# Vjtronics_wo_GND.net
KiCad netlist of a schematic drawn in EAGLE
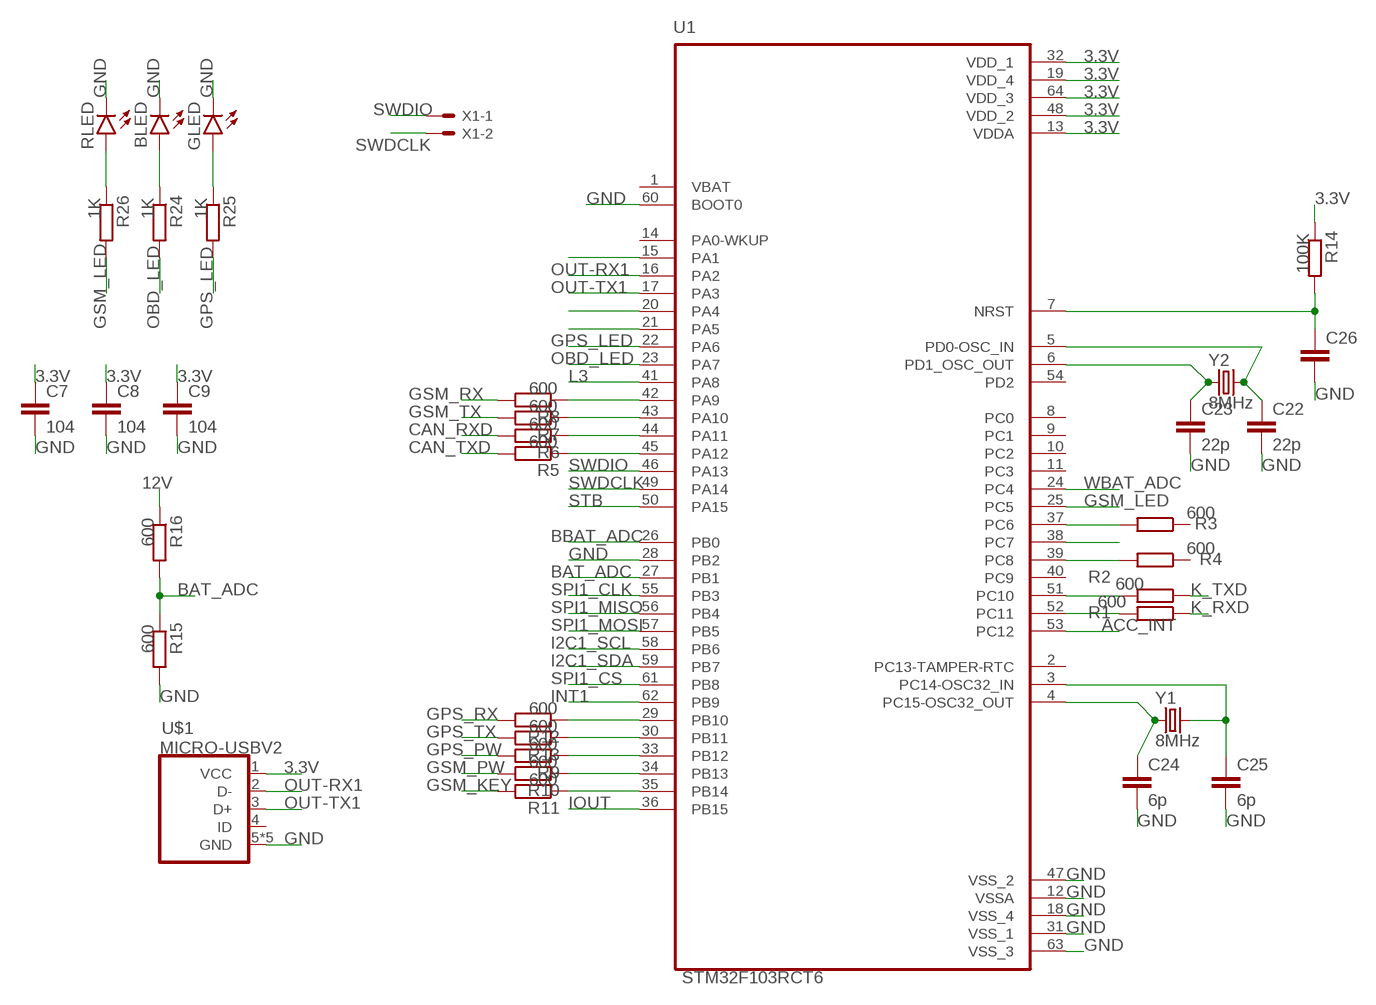
[diagram p0: schematic, sheet 1]

(export (version "E")
  (design (tool "Eeschema 10.0.6"))
  (components
    (comp (ref "BLED")
      (value "LEDCHIPLED_0805")
      (footprint "eagle-import:CHIPLED_0805")
      (libsource (lib "eagle-import") (part "LEDCHIPLED_0805"))
    )
    (comp (ref "C7")
      (value "104")
      (footprint "eagle-import:C0805")
      (libsource (lib "eagle-import") (part "C-EUC0805"))
    )
    (comp (ref "C8")
      (value "104")
      (footprint "eagle-import:C0805")
      (libsource (lib "eagle-import") (part "C-EUC0805"))
    )
    (comp (ref "C9")
      (value "104")
      (footprint "eagle-import:C0805")
      (libsource (lib "eagle-import") (part "C-EUC0805"))
    )
    (comp (ref "C22")
      (value "22p")
      (footprint "eagle-import:C0805")
      (libsource (lib "eagle-import") (part "C-EUC0805"))
    )
    (comp (ref "C23")
      (value "22p")
      (footprint "eagle-import:C0805")
      (libsource (lib "eagle-import") (part "C-EUC0805"))
    )
    (comp (ref "C24")
      (value "6p")
      (footprint "eagle-import:C0805")
      (libsource (lib "eagle-import") (part "C-EUC0805"))
    )
    (comp (ref "C25")
      (value "6p")
      (footprint "eagle-import:C0805")
      (libsource (lib "eagle-import") (part "C-EUC0805"))
    )
    (comp (ref "C26")
      (value "C-EUC0805")
      (footprint "eagle-import:C0805")
      (libsource (lib "eagle-import") (part "C-EUC0805"))
    )
    (comp (ref "GLED")
      (value "LEDCHIPLED_0805")
      (footprint "eagle-import:CHIPLED_0805")
      (libsource (lib "eagle-import") (part "LEDCHIPLED_0805"))
    )
    (comp (ref "R1")
      (value "600")
      (footprint "eagle-import:M0805")
      (libsource (lib "eagle-import") (part "R-EU_M0805"))
    )
    (comp (ref "R2")
      (value "600")
      (footprint "eagle-import:M0805")
      (libsource (lib "eagle-import") (part "R-EU_M0805"))
    )
    (comp (ref "R3")
      (value "600")
      (footprint "eagle-import:M0805")
      (libsource (lib "eagle-import") (part "R-EU_M0805"))
    )
    (comp (ref "R4")
      (value "600")
      (footprint "eagle-import:M0805")
      (libsource (lib "eagle-import") (part "R-EU_M0805"))
    )
    (comp (ref "R5")
      (value "600")
      (footprint "eagle-import:M0805")
      (libsource (lib "eagle-import") (part "R-EU_M0805"))
    )
    (comp (ref "R6")
      (value "600")
      (footprint "eagle-import:M0805")
      (libsource (lib "eagle-import") (part "R-EU_M0805"))
    )
    (comp (ref "R7")
      (value "600")
      (footprint "eagle-import:M0805")
      (libsource (lib "eagle-import") (part "R-EU_M0805"))
    )
    (comp (ref "R8")
      (value "600")
      (footprint "eagle-import:M0805")
      (libsource (lib "eagle-import") (part "R-EU_M0805"))
    )
    (comp (ref "R9")
      (value "600")
      (footprint "eagle-import:M0805")
      (libsource (lib "eagle-import") (part "R-EU_M0805"))
    )
    (comp (ref "R10")
      (value "600")
      (footprint "eagle-import:M0805")
      (libsource (lib "eagle-import") (part "R-EU_M0805"))
    )
    (comp (ref "R11")
      (value "600")
      (footprint "eagle-import:M0805")
      (libsource (lib "eagle-import") (part "R-EU_M0805"))
    )
    (comp (ref "R12")
      (value "600")
      (footprint "eagle-import:M0805")
      (libsource (lib "eagle-import") (part "R-EU_M0805"))
    )
    (comp (ref "R13")
      (value "600")
      (footprint "eagle-import:M0805")
      (libsource (lib "eagle-import") (part "R-EU_M0805"))
    )
    (comp (ref "R14")
      (value "100K")
      (footprint "eagle-import:M0805")
      (libsource (lib "eagle-import") (part "R-EU_M0805"))
    )
    (comp (ref "R15")
      (value "600")
      (footprint "eagle-import:M0805")
      (libsource (lib "eagle-import") (part "R-EU_M0805"))
    )
    (comp (ref "R16")
      (value "600")
      (footprint "eagle-import:M0805")
      (libsource (lib "eagle-import") (part "R-EU_M0805"))
    )
    (comp (ref "R24")
      (value "1K")
      (footprint "eagle-import:M0805")
      (libsource (lib "eagle-import") (part "R-EU_M0805"))
    )
    (comp (ref "R25")
      (value "1K")
      (footprint "eagle-import:M0805")
      (libsource (lib "eagle-import") (part "R-EU_M0805"))
    )
    (comp (ref "R26")
      (value "1K")
      (footprint "eagle-import:M0805")
      (libsource (lib "eagle-import") (part "R-EU_M0805"))
    )
    (comp (ref "RLED")
      (value "LEDCHIPLED_0805")
      (footprint "eagle-import:CHIPLED_0805")
      (libsource (lib "eagle-import") (part "LEDCHIPLED_0805"))
    )
    (comp (ref "U$1")
      (value "MICRO-USBV2")
      (footprint "eagle-import:MICRO-USB-2")
      (libsource (lib "eagle-import") (part "MICRO-USBV2"))
    )
    (comp (ref "U1")
      (value "STM32F103RCT6")
      (footprint "eagle-import:QFP50P1200X1200X160-64N")
      (fields (field (name "MF") "STMicroelectronics"))
      (libsource (lib "eagle-import") (part "STM32F103RCT6"))
    )
    (comp (ref "X1")
      (value "22-23-2021")
      (footprint "eagle-import:22-23-2021")
      (libsource (lib "eagle-import") (part "22-23-2021"))
    )
    (comp (ref "Y1")
      (value "8MHz")
      (footprint "eagle-import:CSM-7X-DU")
      (libsource (lib "eagle-import") (part "CSM-7X-DU"))
    )
    (comp (ref "Y2")
      (value "8MHz")
      (footprint "eagle-import:CSM-7X-DU")
      (libsource (lib "eagle-import") (part "CSM-7X-DU"))
    )
  )
  (nets
    (net (code "1") (name "/3.3V") (class "Default")
      (node (ref "C7") (pin "1") (pinfunction "1_1") (pintype "passive"))
      (node (ref "C8") (pin "1") (pinfunction "1_1") (pintype "passive"))
      (node (ref "C9") (pin "1") (pinfunction "1_1") (pintype "passive"))
      (node (ref "R14") (pin "1") (pinfunction "1_1") (pintype "passive"))
      (node (ref "U$1") (pin "1") (pinfunction "VCC_1") (pintype "power_in"))
      (node (ref "U1") (pin "13") (pinfunction "VDDA_13") (pintype "power_in"))
      (node (ref "U1") (pin "19") (pinfunction "VDD_4_19") (pintype "power_in"))
      (node (ref "U1") (pin "32") (pinfunction "VDD_1_32") (pintype "power_in"))
      (node (ref "U1") (pin "48") (pinfunction "VDD_2_48") (pintype "power_in"))
      (node (ref "U1") (pin "64") (pinfunction "VDD_3_64") (pintype "power_in"))
    )
    (net (code "2") (name "/12V") (class "Default")
      (node (ref "R16") (pin "1") (pinfunction "1_1") (pintype "passive"))
    )
    (net (code "3") (name "/ACC_INT") (class "Default")
      (node (ref "U1") (pin "53") (pinfunction "PC12_53") (pintype "bidirectional"))
    )
    (net (code "4") (name "/BAT_ADC") (class "Default")
      (node (ref "R15") (pin "1") (pinfunction "1_1") (pintype "passive"))
      (node (ref "R16") (pin "2") (pinfunction "2_2") (pintype "passive"))
      (node (ref "U1") (pin "27") (pinfunction "PB1_27") (pintype "bidirectional"))
    )
    (net (code "5") (name "/BBAT_ADC") (class "Default")
      (node (ref "U1") (pin "26") (pinfunction "PB0_26") (pintype "bidirectional"))
    )
    (net (code "6") (name "/CAN_RXD") (class "Default")
      (node (ref "R6") (pin "2") (pinfunction "2_2") (pintype "passive"))
    )
    (net (code "7") (name "/CAN_TXD") (class "Default")
      (node (ref "R5") (pin "2") (pinfunction "2_2") (pintype "passive"))
    )
    (net (code "8") (name "/GND") (class "Default")
      (node (ref "BLED") (pin "C") (pinfunction "C_C") (pintype "passive"))
      (node (ref "C22") (pin "2") (pinfunction "2_2") (pintype "passive"))
      (node (ref "C23") (pin "2") (pinfunction "2_2") (pintype "passive"))
      (node (ref "C24") (pin "2") (pinfunction "2_2") (pintype "passive"))
      (node (ref "C25") (pin "2") (pinfunction "2_2") (pintype "passive"))
      (node (ref "C26") (pin "2") (pinfunction "2_2") (pintype "passive"))
      (node (ref "C7") (pin "2") (pinfunction "2_2") (pintype "passive"))
      (node (ref "C8") (pin "2") (pinfunction "2_2") (pintype "passive"))
      (node (ref "C9") (pin "2") (pinfunction "2_2") (pintype "passive"))
      (node (ref "GLED") (pin "C") (pinfunction "C_C") (pintype "passive"))
      (node (ref "R15") (pin "2") (pinfunction "2_2") (pintype "passive"))
      (node (ref "RLED") (pin "C") (pinfunction "C_C") (pintype "passive"))
      (node (ref "U$1") (pin "5") (pinfunction "GND_5") (pintype "power_in"))
      (node (ref "U$1") (pin "P$1") (pinfunction "GND_P$1") (pintype "power_in"))
      (node (ref "U$1") (pin "P$2") (pinfunction "GND_P$2") (pintype "power_in"))
      (node (ref "U$1") (pin "P$3") (pinfunction "GND_P$3") (pintype "power_in"))
      (node (ref "U$1") (pin "P$4") (pinfunction "GND_P$4") (pintype "power_in"))
      (node (ref "U1") (pin "12") (pinfunction "VSSA_12") (pintype "power_in"))
      (node (ref "U1") (pin "18") (pinfunction "VSS_4_18") (pintype "power_in"))
      (node (ref "U1") (pin "28") (pinfunction "PB2_28") (pintype "bidirectional"))
      (node (ref "U1") (pin "31") (pinfunction "VSS_1_31") (pintype "power_in"))
      (node (ref "U1") (pin "47") (pinfunction "VSS_2_47") (pintype "power_in"))
      (node (ref "U1") (pin "60") (pinfunction "BOOT0_60") (pintype "input"))
      (node (ref "U1") (pin "63") (pinfunction "VSS_3_63") (pintype "power_in"))
    )
    (net (code "9") (name "/GPS_LED") (class "Default")
      (node (ref "R25") (pin "2") (pinfunction "2_2") (pintype "passive"))
      (node (ref "U1") (pin "22") (pinfunction "PA6_22") (pintype "bidirectional"))
    )
    (net (code "10") (name "/GPS_PW") (class "Default")
      (node (ref "R9") (pin "2") (pinfunction "2_2") (pintype "passive"))
    )
    (net (code "11") (name "/GPS_RX") (class "Default")
      (node (ref "R12") (pin "2") (pinfunction "2_2") (pintype "passive"))
    )
    (net (code "12") (name "/GPS_TX") (class "Default")
      (node (ref "R13") (pin "2") (pinfunction "2_2") (pintype "passive"))
    )
    (net (code "13") (name "/GSM_KEY") (class "Default")
      (node (ref "R11") (pin "2") (pinfunction "2_2") (pintype "passive"))
    )
    (net (code "14") (name "/GSM_LED") (class "Default")
      (node (ref "R26") (pin "2") (pinfunction "2_2") (pintype "passive"))
      (node (ref "U1") (pin "25") (pinfunction "PC5_25") (pintype "bidirectional"))
    )
    (net (code "15") (name "/GSM_PW") (class "Default")
      (node (ref "R10") (pin "2") (pinfunction "2_2") (pintype "passive"))
    )
    (net (code "16") (name "/GSM_RX") (class "Default")
      (node (ref "R8") (pin "2") (pinfunction "2_2") (pintype "passive"))
    )
    (net (code "17") (name "/GSM_TX") (class "Default")
      (node (ref "R7") (pin "2") (pinfunction "2_2") (pintype "passive"))
    )
    (net (code "18") (name "/I2C1_SCL") (class "Default")
      (node (ref "U1") (pin "58") (pinfunction "PB6_58") (pintype "bidirectional"))
    )
    (net (code "19") (name "/I2C1_SDA") (class "Default")
      (node (ref "U1") (pin "59") (pinfunction "PB7_59") (pintype "bidirectional"))
    )
    (net (code "20") (name "/INT1") (class "Default")
      (node (ref "U1") (pin "62") (pinfunction "PB9_62") (pintype "bidirectional"))
    )
    (net (code "21") (name "/IOUT") (class "Default")
      (node (ref "U1") (pin "36") (pinfunction "PB15_36") (pintype "bidirectional"))
    )
    (net (code "22") (name "/K_RXD") (class "Default")
      (node (ref "R1") (pin "1") (pinfunction "1_1") (pintype "passive"))
    )
    (net (code "23") (name "/K_TXD") (class "Default")
      (node (ref "R2") (pin "1") (pinfunction "1_1") (pintype "passive"))
    )
    (net (code "24") (name "/L3") (class "Default")
      (node (ref "U1") (pin "41") (pinfunction "PA8_41") (pintype "bidirectional"))
    )
    (net (code "25") (name "/OBD_LED") (class "Default")
      (node (ref "R24") (pin "2") (pinfunction "2_2") (pintype "passive"))
      (node (ref "U1") (pin "23") (pinfunction "PA7_23") (pintype "bidirectional"))
    )
    (net (code "26") (name "/OUT-RX1") (class "Default")
      (node (ref "U$1") (pin "2") (pinfunction "D-_2") (pintype "bidirectional"))
      (node (ref "U1") (pin "16") (pinfunction "PA2_16") (pintype "bidirectional"))
    )
    (net (code "27") (name "/OUT-TX1") (class "Default")
      (node (ref "U$1") (pin "3") (pinfunction "D+_3") (pintype "bidirectional"))
      (node (ref "U1") (pin "17") (pinfunction "PA3_17") (pintype "bidirectional"))
    )
    (net (code "28") (name "/SPI1_CLK") (class "Default")
      (node (ref "U1") (pin "55") (pinfunction "PB3_55") (pintype "bidirectional"))
    )
    (net (code "29") (name "/SPI1_CS") (class "Default")
      (node (ref "U1") (pin "61") (pinfunction "PB8_61") (pintype "bidirectional"))
    )
    (net (code "30") (name "/SPI1_MISO") (class "Default")
      (node (ref "U1") (pin "56") (pinfunction "PB4_56") (pintype "bidirectional"))
    )
    (net (code "31") (name "/SPI1_MOSI") (class "Default")
      (node (ref "U1") (pin "57") (pinfunction "PB5_57") (pintype "bidirectional"))
    )
    (net (code "32") (name "/STB") (class "Default")
      (node (ref "U1") (pin "50") (pinfunction "PA15_50") (pintype "bidirectional"))
    )
    (net (code "33") (name "/SWDCLK") (class "Default")
      (node (ref "U1") (pin "49") (pinfunction "PA14_49") (pintype "bidirectional"))
      (node (ref "X1") (pin "2") (pinfunction "S_2") (pintype "passive"))
    )
    (net (code "34") (name "/SWDIO") (class "Default")
      (node (ref "U1") (pin "46") (pinfunction "PA13_46") (pintype "bidirectional"))
      (node (ref "X1") (pin "1") (pinfunction "S_1") (pintype "passive"))
    )
    (net (code "35") (name "/WBAT_ADC") (class "Default")
      (node (ref "U1") (pin "24") (pinfunction "PC4_24") (pintype "bidirectional"))
    )
    (net (code "36") (name "Net-(BLED-PadA)") (class "Default")
      (node (ref "BLED") (pin "A") (pinfunction "A_A") (pintype "passive"))
      (node (ref "R24") (pin "1") (pinfunction "1_1") (pintype "passive"))
    )
    (net (code "37") (name "Net-(GLED-PadA)") (class "Default")
      (node (ref "GLED") (pin "A") (pinfunction "A_A") (pintype "passive"))
      (node (ref "R25") (pin "1") (pinfunction "1_1") (pintype "passive"))
    )
    (net (code "38") (name "Net-(R26-Pad1)") (class "Default")
      (node (ref "R26") (pin "1") (pinfunction "1_1") (pintype "passive"))
      (node (ref "RLED") (pin "A") (pinfunction "A_A") (pintype "passive"))
    )
    (net (code "39") (name "Net-(U1-NRST)") (class "Default")
      (node (ref "C26") (pin "1") (pinfunction "1_1") (pintype "passive"))
      (node (ref "R14") (pin "2") (pinfunction "2_2") (pintype "passive"))
      (node (ref "U1") (pin "7") (pinfunction "NRST_7") (pintype "input"))
    )
    (net (code "40") (name "Net-(U1-PA9)") (class "Default")
      (node (ref "R8") (pin "1") (pinfunction "1_1") (pintype "passive"))
      (node (ref "U1") (pin "42") (pinfunction "PA9_42") (pintype "bidirectional"))
    )
    (net (code "41") (name "Net-(U1-PA10)") (class "Default")
      (node (ref "R7") (pin "1") (pinfunction "1_1") (pintype "passive"))
      (node (ref "U1") (pin "43") (pinfunction "PA10_43") (pintype "bidirectional"))
    )
    (net (code "42") (name "Net-(U1-PA11)") (class "Default")
      (node (ref "R6") (pin "1") (pinfunction "1_1") (pintype "passive"))
      (node (ref "U1") (pin "44") (pinfunction "PA11_44") (pintype "bidirectional"))
    )
    (net (code "43") (name "Net-(U1-PA12)") (class "Default")
      (node (ref "R5") (pin "1") (pinfunction "1_1") (pintype "passive"))
      (node (ref "U1") (pin "45") (pinfunction "PA12_45") (pintype "bidirectional"))
    )
    (net (code "44") (name "Net-(U1-PB10)") (class "Default")
      (node (ref "R12") (pin "1") (pinfunction "1_1") (pintype "passive"))
      (node (ref "U1") (pin "29") (pinfunction "PB10_29") (pintype "bidirectional"))
    )
    (net (code "45") (name "Net-(U1-PB11)") (class "Default")
      (node (ref "R13") (pin "1") (pinfunction "1_1") (pintype "passive"))
      (node (ref "U1") (pin "30") (pinfunction "PB11_30") (pintype "bidirectional"))
    )
    (net (code "46") (name "Net-(U1-PB12)") (class "Default")
      (node (ref "R9") (pin "1") (pinfunction "1_1") (pintype "passive"))
      (node (ref "U1") (pin "33") (pinfunction "PB12_33") (pintype "bidirectional"))
    )
    (net (code "47") (name "Net-(U1-PB13)") (class "Default")
      (node (ref "R10") (pin "1") (pinfunction "1_1") (pintype "passive"))
      (node (ref "U1") (pin "34") (pinfunction "PB13_34") (pintype "bidirectional"))
    )
    (net (code "48") (name "Net-(U1-PB14)") (class "Default")
      (node (ref "R11") (pin "1") (pinfunction "1_1") (pintype "passive"))
      (node (ref "U1") (pin "35") (pinfunction "PB14_35") (pintype "bidirectional"))
    )
    (net (code "49") (name "Net-(U1-PC6)") (class "Default")
      (node (ref "R3") (pin "2") (pinfunction "2_2") (pintype "passive"))
      (node (ref "U1") (pin "37") (pinfunction "PC6_37") (pintype "bidirectional"))
    )
    (net (code "50") (name "Net-(U1-PC8)") (class "Default")
      (node (ref "R4") (pin "2") (pinfunction "2_2") (pintype "passive"))
      (node (ref "U1") (pin "39") (pinfunction "PC8_39") (pintype "bidirectional"))
    )
    (net (code "51") (name "Net-(U1-PC10)") (class "Default")
      (node (ref "R2") (pin "2") (pinfunction "2_2") (pintype "passive"))
      (node (ref "U1") (pin "51") (pinfunction "PC10_51") (pintype "bidirectional"))
    )
    (net (code "52") (name "Net-(U1-PC11)") (class "Default")
      (node (ref "R1") (pin "2") (pinfunction "2_2") (pintype "passive"))
      (node (ref "U1") (pin "52") (pinfunction "PC11_52") (pintype "bidirectional"))
    )
    (net (code "53") (name "Net-(U1-PC14-OSC32_IN)") (class "Default")
      (node (ref "C25") (pin "1") (pinfunction "1_1") (pintype "passive"))
      (node (ref "U1") (pin "3") (pinfunction "PC14-OSC32_IN_3") (pintype "bidirectional"))
      (node (ref "Y1") (pin "2") (pinfunction "2_2") (pintype "passive"))
    )
    (net (code "54") (name "Net-(U1-PC15-OSC32_OUT)") (class "Default")
      (node (ref "C24") (pin "1") (pinfunction "1_1") (pintype "passive"))
      (node (ref "U1") (pin "4") (pinfunction "PC15-OSC32_OUT_4") (pintype "bidirectional"))
      (node (ref "Y1") (pin "1") (pinfunction "1_1") (pintype "passive"))
    )
    (net (code "55") (name "Net-(U1-PD0-OSC_IN)") (class "Default")
      (node (ref "C22") (pin "1") (pinfunction "1_1") (pintype "passive"))
      (node (ref "U1") (pin "5") (pinfunction "PD0-OSC_IN_5") (pintype "input"))
      (node (ref "Y2") (pin "2") (pinfunction "2_2") (pintype "passive"))
    )
    (net (code "56") (name "Net-(U1-PD1_OSC_OUT)") (class "Default")
      (node (ref "C23") (pin "1") (pinfunction "1_1") (pintype "passive"))
      (node (ref "U1") (pin "6") (pinfunction "PD1_OSC_OUT_6") (pintype "output"))
      (node (ref "Y2") (pin "1") (pinfunction "1_1") (pintype "passive"))
    )
    (net (code "57") (name "unconnected-(R3-Pad1)") (class "Default")
      (node (ref "R3") (pin "1") (pinfunction "1_1") (pintype "passive"))
    )
    (net (code "58") (name "unconnected-(R4-Pad1)") (class "Default")
      (node (ref "R4") (pin "1") (pinfunction "1_1") (pintype "passive"))
    )
    (net (code "59") (name "unconnected-(U$1-ID-Pad4)") (class "Default")
      (node (ref "U$1") (pin "4") (pinfunction "ID_4") (pintype "bidirectional"))
    )
    (net (code "60") (name "unconnected-(U1-PA0-WKUP-Pad14)") (class "Default")
      (node (ref "U1") (pin "14") (pinfunction "PA0-WKUP_14") (pintype "bidirectional"))
    )
    (net (code "61") (name "unconnected-(U1-PA1-Pad15)") (class "Default")
      (node (ref "U1") (pin "15") (pinfunction "PA1_15") (pintype "bidirectional"))
    )
    (net (code "62") (name "unconnected-(U1-PA4-Pad20)") (class "Default")
      (node (ref "U1") (pin "20") (pinfunction "PA4_20") (pintype "bidirectional"))
    )
    (net (code "63") (name "unconnected-(U1-PA5-Pad21)") (class "Default")
      (node (ref "U1") (pin "21") (pinfunction "PA5_21") (pintype "bidirectional"))
    )
    (net (code "64") (name "unconnected-(U1-PC0-Pad8)") (class "Default")
      (node (ref "U1") (pin "8") (pinfunction "PC0_8") (pintype "bidirectional"))
    )
    (net (code "65") (name "unconnected-(U1-PC1-Pad9)") (class "Default")
      (node (ref "U1") (pin "9") (pinfunction "PC1_9") (pintype "bidirectional"))
    )
    (net (code "66") (name "unconnected-(U1-PC2-Pad10)") (class "Default")
      (node (ref "U1") (pin "10") (pinfunction "PC2_10") (pintype "bidirectional"))
    )
    (net (code "67") (name "unconnected-(U1-PC3-Pad11)") (class "Default")
      (node (ref "U1") (pin "11") (pinfunction "PC3_11") (pintype "bidirectional"))
    )
    (net (code "68") (name "unconnected-(U1-PC7-Pad38)") (class "Default")
      (node (ref "U1") (pin "38") (pinfunction "PC7_38") (pintype "bidirectional"))
    )
    (net (code "69") (name "unconnected-(U1-PC9-Pad40)") (class "Default")
      (node (ref "U1") (pin "40") (pinfunction "PC9_40") (pintype "bidirectional"))
    )
    (net (code "70") (name "unconnected-(U1-PC13-TAMPER-RTC-Pad2)") (class "Default")
      (node (ref "U1") (pin "2") (pinfunction "PC13-TAMPER-RTC_2") (pintype "bidirectional"))
    )
    (net (code "71") (name "unconnected-(U1-PD2-Pad54)") (class "Default")
      (node (ref "U1") (pin "54") (pinfunction "PD2_54") (pintype "bidirectional"))
    )
    (net (code "72") (name "unconnected-(U1-VBAT-Pad1)") (class "Default")
      (node (ref "U1") (pin "1") (pinfunction "VBAT_1") (pintype "input"))
    )
  )
)
